# r5.net
KiCad netlist of a schematic drawn in EasyEDA
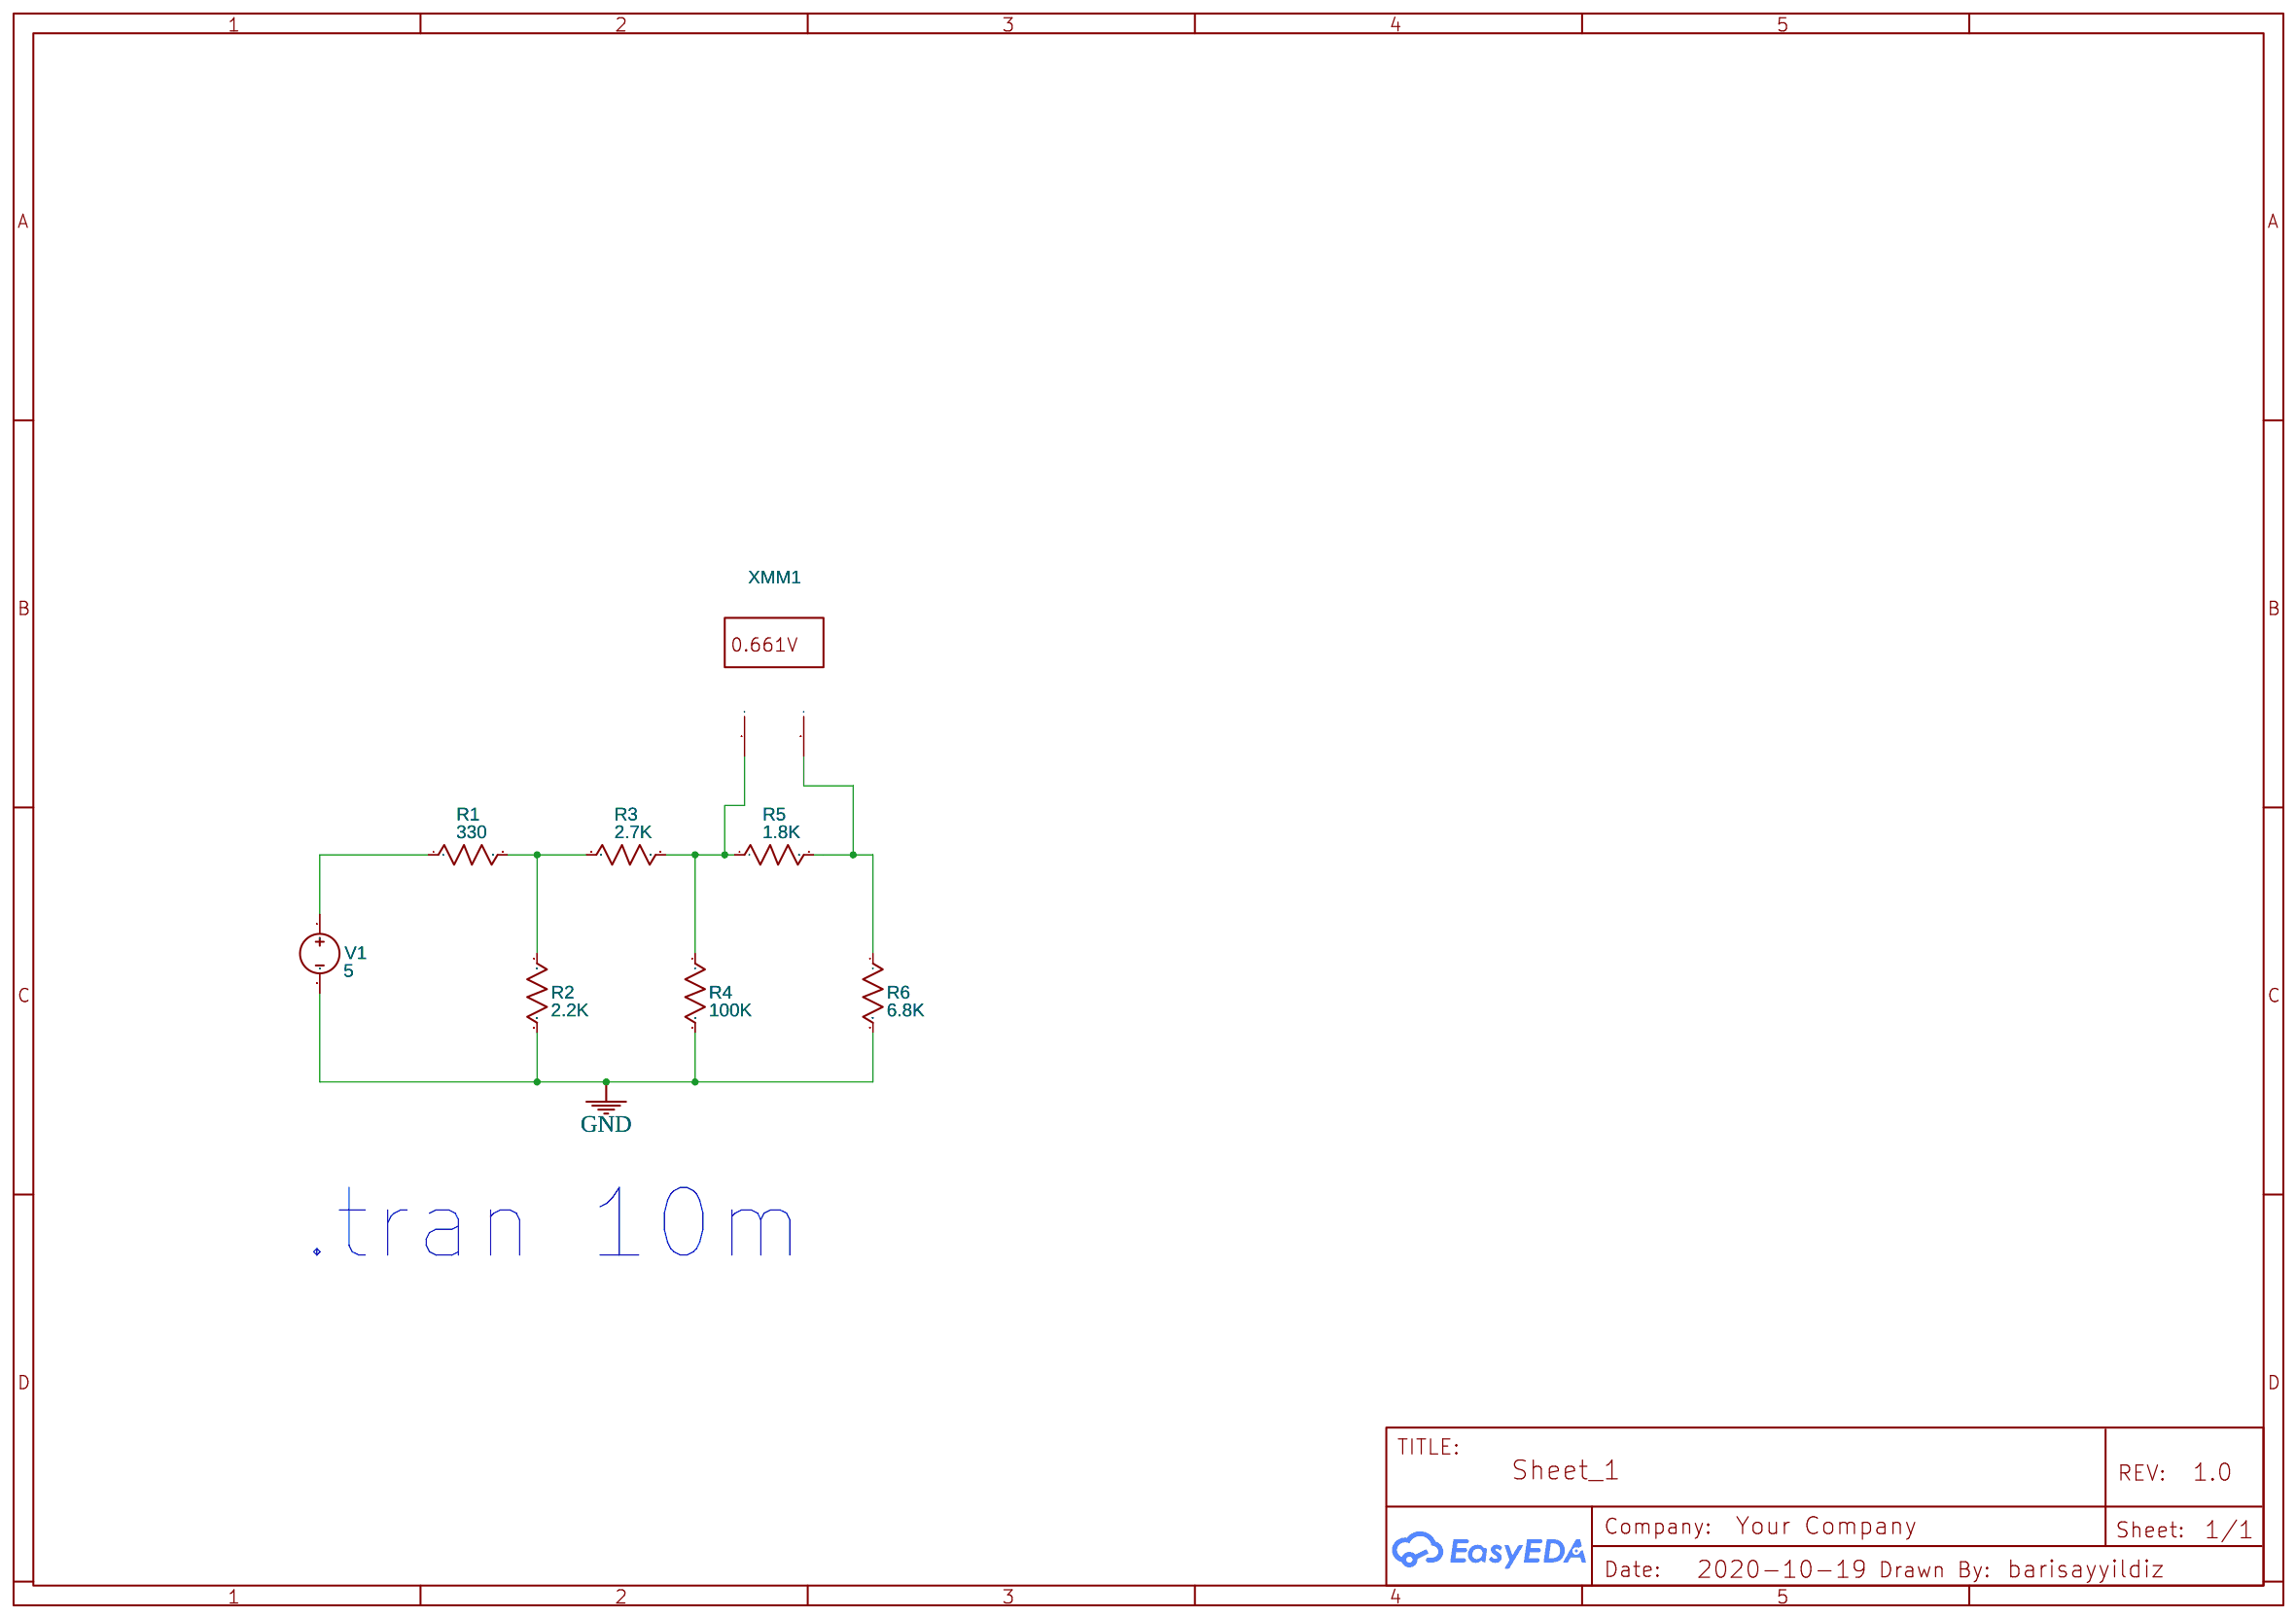
[diagram p0: schematic sheet]

(export (version "E")
  (design (tool "Eeschema 10.0.6"))
  (components
    (comp (ref "R1") (value "330") (libsource (lib "") (part "Resistor_US_1")))
    (comp (ref "R2") (value "2.2K") (libsource (lib "") (part "Resistor_US")))
    (comp (ref "R3") (value "2.7K") (libsource (lib "") (part "Resistor_US_1")))
    (comp (ref "R4") (value "100K") (libsource (lib "") (part "Resistor_US")))
    (comp (ref "R5") (value "1.8K") (libsource (lib "") (part "Resistor_US_1")))
    (comp (ref "R6") (value "6.8K") (libsource (lib "") (part "Resistor_US")))
    (comp (ref "V1") (value "5") (libsource (lib "") (part "VDC")))
    (comp (ref "XMM1") (value "Multimeter") (libsource (lib "") (part "MULTIMETER")))
  )
  (nets
    (net (code "1") (name "GND") (class "Default")
      (node (ref "R2") (pin "2") (pinfunction "2_2") (pintype "unspecified"))
      (node (ref "R4") (pin "2") (pinfunction "2_2") (pintype "unspecified"))
      (node (ref "R6") (pin "2") (pinfunction "2_2") (pintype "unspecified"))
      (node (ref "V1") (pin "2") (pinfunction "2_2") (pintype "unspecified"))
    )
    (net (code "2") (name "Net-(R1-Pad1)") (class "Default")
      (node (ref "R1") (pin "1") (pinfunction "1_1") (pintype "unspecified"))
      (node (ref "V1") (pin "1") (pinfunction "1_1") (pintype "unspecified"))
    )
    (net (code "3") (name "Net-(R1-Pad2)") (class "Default")
      (node (ref "R1") (pin "2") (pinfunction "2_2") (pintype "unspecified"))
      (node (ref "R2") (pin "1") (pinfunction "1_1") (pintype "unspecified"))
      (node (ref "R3") (pin "1") (pinfunction "1_1") (pintype "unspecified"))
    )
    (net (code "4") (name "Net-(XMM1-+)") (class "Default")
      (node (ref "R3") (pin "2") (pinfunction "2_2") (pintype "unspecified"))
      (node (ref "R4") (pin "1") (pinfunction "1_1") (pintype "unspecified"))
      (node (ref "R5") (pin "1") (pinfunction "1_1") (pintype "unspecified"))
      (node (ref "XMM1") (pin "1") (pinfunction "+_1") (pintype "unspecified"))
    )
    (net (code "5") (name "Net-(XMM1-I)") (class "Default")
      (node (ref "R5") (pin "2") (pinfunction "2_2") (pintype "unspecified"))
      (node (ref "R6") (pin "1") (pinfunction "1_1") (pintype "unspecified"))
      (node (ref "XMM1") (pin "2") (pinfunction "I_2") (pintype "unspecified"))
    )
  )
)
